# Accelerometer_3-Axis.net
KiCad netlist of a schematic drawn in EAGLE
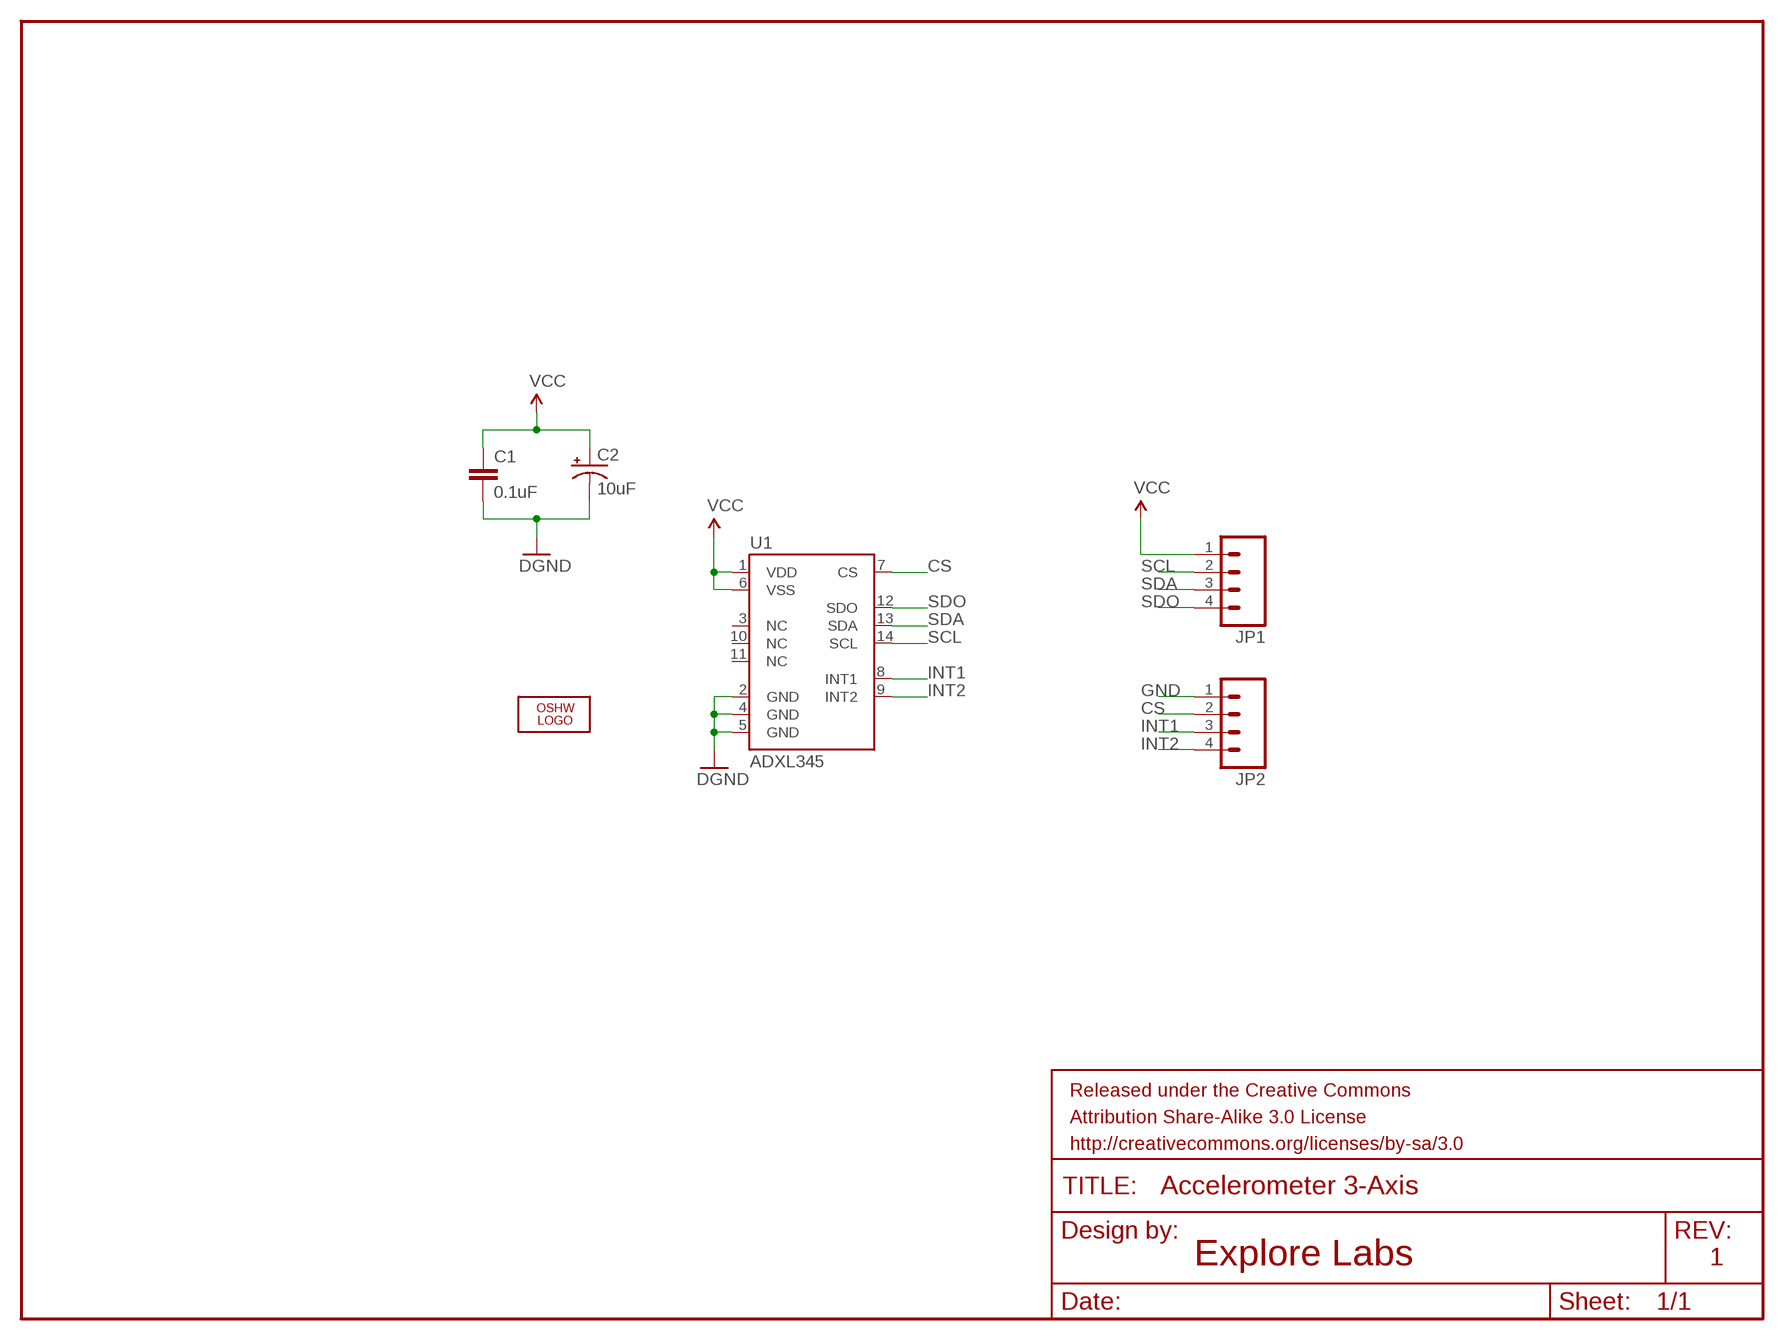
[diagram p0: schematic, sheet 1]

(export (version "E")
  (design (tool "Eeschema 10.0.6"))
  (components
    (comp (ref "C1")
      (value "0.1uF")
      (footprint "eagle-import:0402-CAP")
      (libsource (lib "eagle-import") (part "CAP0402-CAP"))
    )
    (comp (ref "C2")
      (value "10uF")
      (footprint "eagle-import:EIA3216")
      (libsource (lib "eagle-import") (part "CAP_POL1206"))
    )
    (comp (ref "JP1")
      (value "M04PTH")
      (footprint "eagle-import:1X04")
      (libsource (lib "eagle-import") (part "M04PTH"))
    )
    (comp (ref "JP2")
      (value "M04PTH")
      (footprint "eagle-import:1X04")
      (libsource (lib "eagle-import") (part "M04PTH"))
    )
    (comp (ref "LOGO2")
      (value "OSHW_LOGO_FILLX0100-NT")
      (footprint "eagle-import:OSHW_FILLX100_NOTEXT")
      (libsource (lib "eagle-import") (part "OSHW_LOGO_FILLX0100-NT"))
    )
    (comp (ref "U1")
      (value "ADXL345")
      (footprint "eagle-import:LGA14")
      (libsource (lib "eagle-import") (part "ADXL345"))
    )
  )
  (nets
    (net (code "1") (name "/CS") (class "Default")
      (node (ref "JP2") (pin "2") (pinfunction "2_2") (pintype "passive"))
      (node (ref "U1") (pin "7") (pinfunction "CS_7") (pintype "bidirectional"))
    )
    (net (code "2") (name "/INT1") (class "Default")
      (node (ref "JP2") (pin "3") (pinfunction "3_3") (pintype "passive"))
      (node (ref "U1") (pin "8") (pinfunction "INT1_8") (pintype "bidirectional"))
    )
    (net (code "3") (name "/INT2") (class "Default")
      (node (ref "JP2") (pin "4") (pinfunction "4_4") (pintype "passive"))
      (node (ref "U1") (pin "9") (pinfunction "INT2_9") (pintype "bidirectional"))
    )
    (net (code "4") (name "/SCL") (class "Default")
      (node (ref "JP1") (pin "2") (pinfunction "2_2") (pintype "passive"))
      (node (ref "U1") (pin "14") (pinfunction "SCL_14") (pintype "bidirectional"))
    )
    (net (code "5") (name "/SDA") (class "Default")
      (node (ref "JP1") (pin "3") (pinfunction "3_3") (pintype "passive"))
      (node (ref "U1") (pin "13") (pinfunction "SDA_13") (pintype "bidirectional"))
    )
    (net (code "6") (name "/SDO") (class "Default")
      (node (ref "JP1") (pin "4") (pinfunction "4_4") (pintype "passive"))
      (node (ref "U1") (pin "12") (pinfunction "SDO_12") (pintype "bidirectional"))
    )
    (net (code "7") (name "DGND") (class "Default")
      (node (ref "C1") (pin "2") (pinfunction "2_2") (pintype "passive"))
      (node (ref "C2") (pin "C") (pinfunction "-_C") (pintype "passive"))
      (node (ref "JP2") (pin "1") (pinfunction "1_1") (pintype "passive"))
      (node (ref "U1") (pin "2") (pinfunction "GND_2") (pintype "bidirectional"))
      (node (ref "U1") (pin "4") (pinfunction "GND_4") (pintype "bidirectional"))
      (node (ref "U1") (pin "5") (pinfunction "GND_5") (pintype "bidirectional"))
    )
    (net (code "8") (name "VCC") (class "Default")
      (node (ref "C1") (pin "1") (pinfunction "1_1") (pintype "passive"))
      (node (ref "C2") (pin "A") (pinfunction "+_A") (pintype "passive"))
      (node (ref "JP1") (pin "1") (pinfunction "1_1") (pintype "passive"))
      (node (ref "U1") (pin "1") (pinfunction "VDD_1") (pintype "bidirectional"))
      (node (ref "U1") (pin "6") (pinfunction "VSS_6") (pintype "bidirectional"))
    )
    (net (code "9") (name "unconnected-(U1-NC-Pad3)") (class "Default")
      (node (ref "U1") (pin "3") (pinfunction "NC_3") (pintype "bidirectional"))
    )
    (net (code "10") (name "unconnected-(U1-NC-Pad10)") (class "Default")
      (node (ref "U1") (pin "10") (pinfunction "NC_10") (pintype "bidirectional"))
    )
    (net (code "11") (name "unconnected-(U1-NC-Pad11)") (class "Default")
      (node (ref "U1") (pin "11") (pinfunction "NC_11") (pintype "bidirectional"))
    )
  )
)
